# DOut_Isolator.net
KiCad netlist of a schematic drawn in Altium Designer
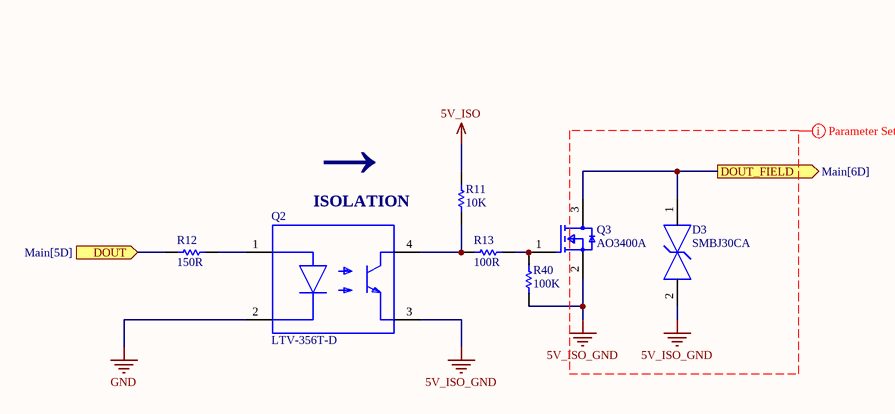
[diagram p0: DOut_Isolator.SchDoc]

(export (version "E")
  (design (tool "Eeschema 10.0.6"))
  (components
    (comp (ref "D3")
      (value "SMBJ30CA")
      (footprint "FP-SMBJ30CAHE3-52-MFG")
      (description "TVS DIODE 30V 48.4V DO214AA")
      (fields
        (field (name "OCTOPART") "https://octopart.com/smbj30cahe3%2F52-vishay-43725255")
        (field (name "MANUFACTURER") "Vishay Semiconductor Diodes Division")
      )
      (libsource (lib "Altium Content Vault") (part "876f4347bf90aa6f500f43e3cd03972"))
    )
    (comp (ref "Q2")
      (value "LTV-356T-D")
      (footprint "FP-LTV-356T-D-MFG")
      (description "OPTOCPL 1 CH TRAN OUT SMT")
      (fields
        (field (name "MANUFACTURER") "Lite-On")
        (field (name "OCTOPART") "https://octopart.com/ltv-356t-d-lite-on-11764243")
      )
      (libsource (lib "Altium Content Vault") (part "34aec040319b23b6d7df8c049769266"))
    )
    (comp (ref "Q3")
      (value "AO3400A")
      (footprint "FP-SOT23-MFG")
      (description "MOSFET N-CH 30V 5.7A SOT23")
      (libsource (lib "Altium Content Vault") (part "0a9ea7c96deaaede766a5b531c28de0"))
    )
    (comp (ref "R11")
      (value "10K")
      (footprint "RESC1609X55X30LL15T15")
      (description "Chip Resistor, 10 KOhm, +/- 1%, 0.1 W, -55 to 155 degC, 0603 (1608 Metric), RoHS, Tape and Reel")
      (fields (field (name "TOLERANCE") "1%") (field (name "MANUFACTURER") "Panasonic"))
      (libsource (lib "Altium Content Vault") (part "RES-2"))
    )
    (comp (ref "R12")
      (value "150R")
      (footprint "RESC1608X55X30ML20T20")
      (fields (field (name "PART NUMBER") "ERA3AEB151V") (field (name "MANUFACTURER") "Panasonic"))
      (libsource (lib "Altium Content Vault") (part "RES"))
    )
    (comp (ref "R13")
      (value "100R")
      (footprint "RESC1609X50X30ML8T20")
      (description "Chip Resistor, 100 Ohm, +/- 1%, 100 mW,-55 to 155 degC, 0603 (1608 Metric), RoHS, Tape and Ree")
      (fields (field (name "MANUFACTURER") "Vishay Semiconductor"))
      (libsource (lib "Altium Content Vault") (part "RES-2"))
    )
    (comp (ref "R40")
      (value "100K")
      (footprint "RESC1608X55X30ML15T15")
      (fields (field (name "PART NUMBER") "ERJ-3EKF1003V") (field (name "MANUFACTURER") "Panasonic"))
      (libsource (lib "Altium Content Vault") (part "RES"))
    )
  )
  (nets
    (net (code "1") (name "/DOUT") (class "Default")
      (node (ref "R12") (pin "1") (pinfunction "1_1") (pintype "passive"))
    )
    (net (code "2") (name "/DOUT_FIELD") (class "Default")
      (node (ref "D3") (pin "1") (pinfunction "1_1") (pintype "passive"))
      (node (ref "Q3") (pin "3") (pinfunction "D_3") (pintype "passive"))
    )
    (net (code "3") (name "5V_ISO") (class "Default")
      (node (ref "R11") (pin "1") (pinfunction "1_1") (pintype "passive"))
    )
    (net (code "4") (name "5V_ISO_GND") (class "Default")
      (node (ref "D3") (pin "2") (pinfunction "2_2") (pintype "passive"))
      (node (ref "Q2") (pin "3") (pinfunction "E_3") (pintype "passive"))
      (node (ref "Q3") (pin "2") (pinfunction "S_2") (pintype "passive"))
      (node (ref "R40") (pin "2") (pinfunction "2_2") (pintype "passive"))
    )
    (net (code "5") (name "GND") (class "Default")
      (node (ref "Q2") (pin "2") (pinfunction "C_2") (pintype "passive"))
    )
    (net (code "6") (name "Net-(Q2-A)") (class "Default")
      (node (ref "Q2") (pin "1") (pinfunction "A_1") (pintype "passive"))
      (node (ref "R12") (pin "2") (pinfunction "2_2") (pintype "passive"))
    )
    (net (code "7") (name "Net-(Q2-C-Pad4)") (class "Default")
      (node (ref "Q2") (pin "4") (pinfunction "C_4") (pintype "passive"))
      (node (ref "R11") (pin "2") (pinfunction "2_2") (pintype "passive"))
      (node (ref "R13") (pin "1") (pinfunction "1_1") (pintype "passive"))
    )
    (net (code "8") (name "Net-(Q3-G)") (class "Default")
      (node (ref "Q3") (pin "1") (pinfunction "G_1") (pintype "passive"))
      (node (ref "R13") (pin "2") (pinfunction "2_2") (pintype "passive"))
      (node (ref "R40") (pin "1") (pinfunction "1_1") (pintype "passive"))
    )
  )
)
